# SmartGarden_PCB.net
KiCad netlist of a schematic drawn in Altium Designer
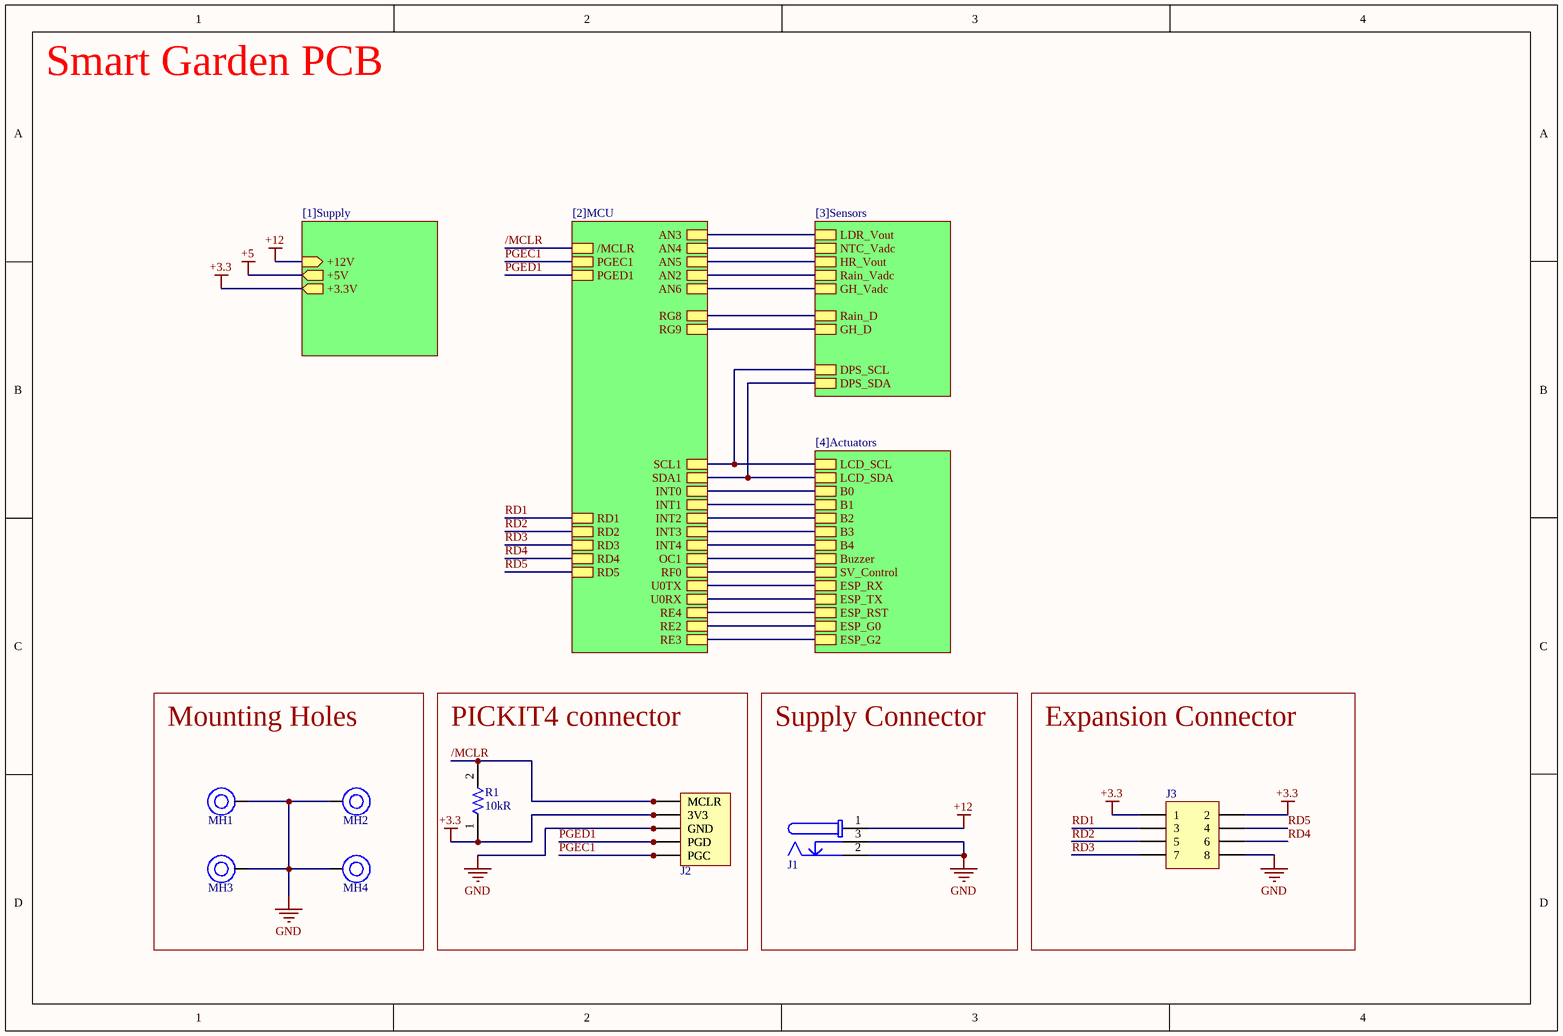
[diagram p0: SmartGarden_PCB.SchDoc]

(export (version "E")
  (design (tool "Eeschema 10.0.6"))
  (components
    (comp (ref "J1")
      (value "694108301002")
      (footprint "694108301002")
      (description "WR-DC DC Power Jack Connector, Male, Right Angled, 24V, 5A")
      (fields (field (name "MANUFACTURER") "Wurth Elektronik"))
      (libsource (lib "CommonFiles_Library") (part "694108301002"))
    )
    (comp (ref "J2")
      (value "61300511121")
      (footprint "J_PinHeader_1x5")
      (description "THT Vertical Pin Header WR-PHD, Pitch 2.54 mm, Single Row, 5 pins")
      (fields (field (name "MANUFACTURER") "Molex") (field (name ".CREATOR") "GP"))
      (libsource (lib "Electromechanical") (part "J_Pickit3"))
    )
    (comp (ref "J3")
      (value "J_DualSocketHeader_8")
      (footprint "Dual socket header 8 pins")
      (libsource (lib "CommonFiles_Library") (part "J_DualSocketHeader_8"))
    )
    (comp (ref "MH1")
      (value "Mounting_Hole_M3")
      (footprint "Mounting_Hole_M3")
      (libsource (lib "Electromechanical") (part "Mounting_Hole_M3"))
    )
    (comp (ref "MH2")
      (value "Mounting_Hole_M3")
      (footprint "Mounting_Hole_M3")
      (libsource (lib "Electromechanical") (part "Mounting_Hole_M3"))
    )
    (comp (ref "MH3")
      (value "Mounting_Hole_M3")
      (footprint "Mounting_Hole_M3")
      (libsource (lib "Electromechanical") (part "Mounting_Hole_M3"))
    )
    (comp (ref "MH4")
      (value "Mounting_Hole_M3")
      (footprint "Mounting_Hole_M3")
      (libsource (lib "Electromechanical") (part "Mounting_Hole_M3"))
    )
    (comp (ref "R1")
      (value "CR0805-JW-103ELF")
      (footprint "R0805FTK")
      (fields
        (field (name "TOLERANCE") "5%")
        (field (name "RESISTANCE") "10kR")
        (field (name ".CREATOR") "DR")
      )
      (libsource (lib "Passives") (part "R10k-0805FTK"))
    )
  )
  (nets
    (net (code "1") (name "+3.3") (class "Default")
      (node (ref "J2") (pin "2") (pinfunction "3V3_2") (pintype "passive"))
      (node (ref "J3") (pin "1") (pinfunction "1_1") (pintype "passive"))
      (node (ref "J3") (pin "2") (pinfunction "2_2") (pintype "passive"))
      (node (ref "R1") (pin "1") (pinfunction "1_1") (pintype "passive"))
    )
    (net (code "3") (name "+12") (class "Default")
      (node (ref "J1") (pin "1") (pinfunction "1_1") (pintype "passive"))
    )
    (net (code "23") (name "/PGEC1") (class "Default")
      (node (ref "J2") (pin "5") (pinfunction "PGC_5") (pintype "passive"))
    )
    (net (code "24") (name "/PGED1") (class "Default")
      (node (ref "J2") (pin "4") (pinfunction "PGD_4") (pintype "passive"))
    )
    (net (code "25") (name "/RD1") (class "Default")
      (node (ref "J3") (pin "3") (pinfunction "3_3") (pintype "passive"))
    )
    (net (code "26") (name "/RD2") (class "Default")
      (node (ref "J3") (pin "5") (pinfunction "5_5") (pintype "passive"))
    )
    (net (code "27") (name "/RD3") (class "Default")
      (node (ref "J3") (pin "7") (pinfunction "7_7") (pintype "passive"))
    )
    (net (code "28") (name "/RD4") (class "Default")
      (node (ref "J3") (pin "6") (pinfunction "6_6") (pintype "passive"))
    )
    (net (code "29") (name "/RD5") (class "Default")
      (node (ref "J3") (pin "4") (pinfunction "4_4") (pintype "passive"))
    )
    (net (code "32") (name "/{slash}MCLR") (class "Default")
      (node (ref "J2") (pin "1") (pinfunction "MCLR_1") (pintype "passive"))
      (node (ref "R1") (pin "2") (pinfunction "2_2") (pintype "passive"))
    )
    (net (code "33") (name "GND") (class "Default")
      (node (ref "J1") (pin "2") (pinfunction "2_2") (pintype "passive"))
      (node (ref "J1") (pin "3") (pinfunction "3_3") (pintype "passive"))
      (node (ref "J2") (pin "3") (pinfunction "GND_3") (pintype "passive"))
      (node (ref "J3") (pin "8") (pinfunction "8_8") (pintype "passive"))
      (node (ref "MH1") (pin "1") (pinfunction "1_1") (pintype "passive"))
      (node (ref "MH2") (pin "1") (pinfunction "1_1") (pintype "passive"))
      (node (ref "MH3") (pin "1") (pinfunction "1_1") (pintype "passive"))
      (node (ref "MH4") (pin "1") (pinfunction "1_1") (pintype "passive"))
    )
  )
)
